# SR_Presentation_Version.net
KiCad netlist of a schematic drawn in EAGLE
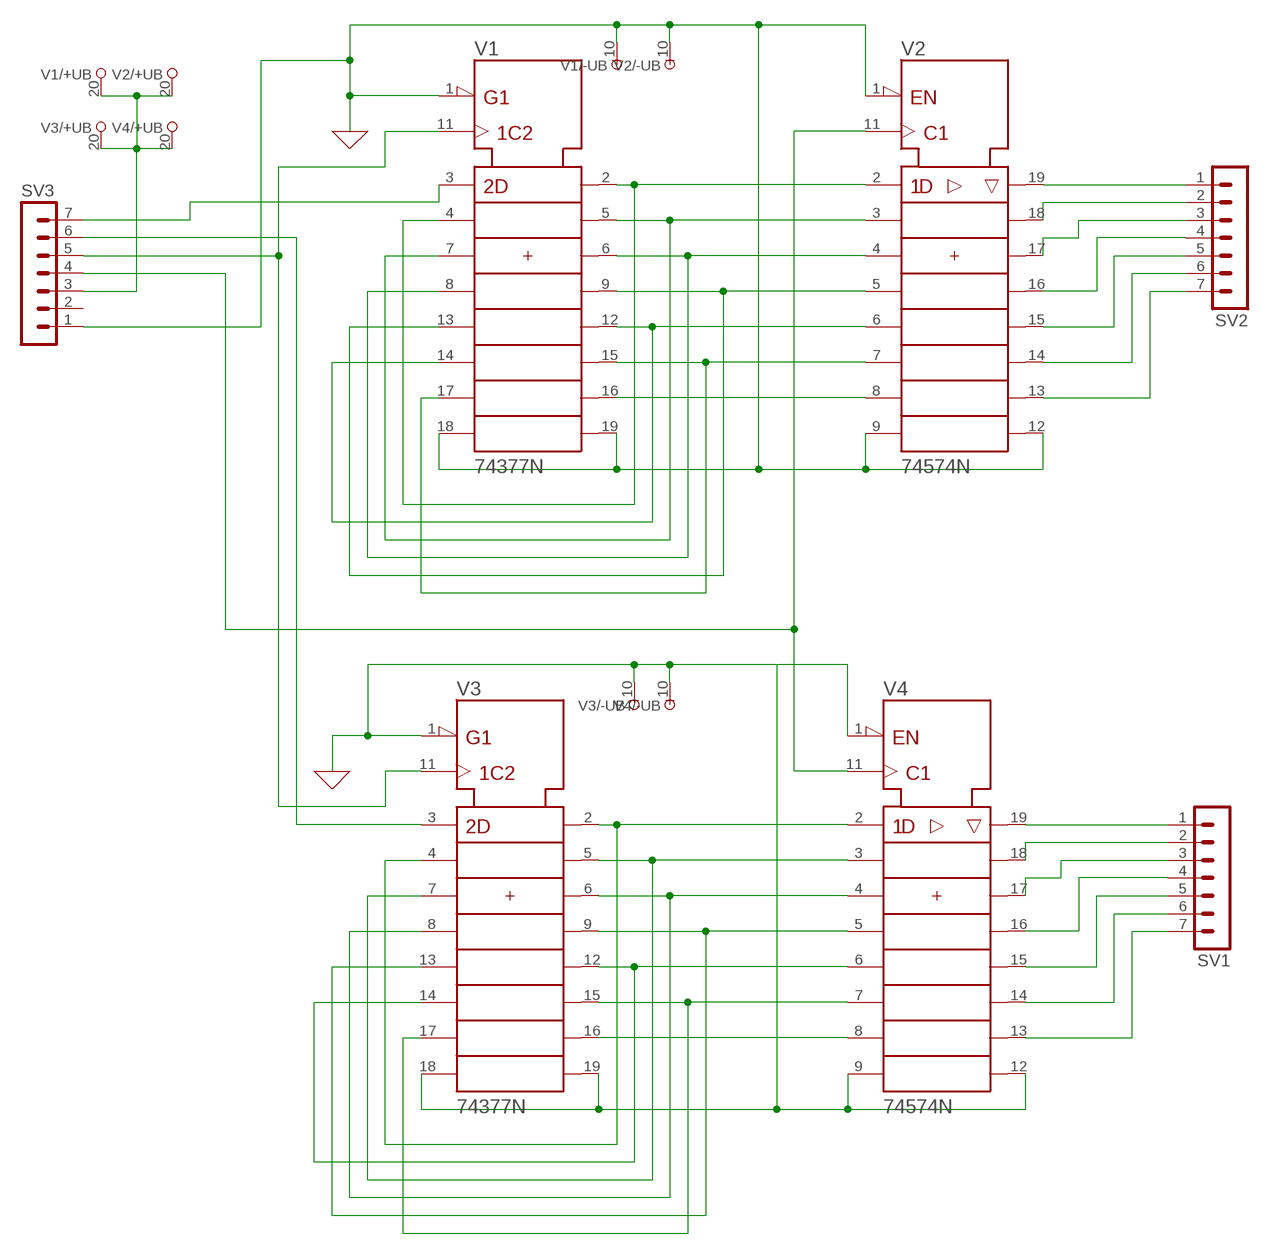
[diagram p0: schematic, sheet 1]

(export (version "E")
  (design (tool "Eeschema 10.0.6"))
  (components
    (comp (ref "SV1")
      (value "MA07-1")
      (footprint "eagle-import:MA07-1")
      (libsource (lib "eagle-import") (part "MA07-1"))
    )
    (comp (ref "SV2")
      (value "MA07-1")
      (footprint "eagle-import:MA07-1")
      (libsource (lib "eagle-import") (part "MA07-1"))
    )
    (comp (ref "SV3")
      (value "MA07-1")
      (footprint "eagle-import:MA07-1")
      (libsource (lib "eagle-import") (part "MA07-1"))
    )
    (comp (ref "V1")
      (value "74377N")
      (footprint "eagle-import:DIL20")
      (libsource (lib "eagle-import") (part "74377N"))
    )
    (comp (ref "V2")
      (value "74574N")
      (footprint "eagle-import:DIL20")
      (libsource (lib "eagle-import") (part "74574N"))
    )
    (comp (ref "V3")
      (value "74377N")
      (footprint "eagle-import:DIL20")
      (libsource (lib "eagle-import") (part "74377N"))
    )
    (comp (ref "V4")
      (value "74574N")
      (footprint "eagle-import:DIL20")
      (libsource (lib "eagle-import") (part "74574N"))
    )
  )
  (nets
    (net (code "1") (name "GND") (class "Default")
      (node (ref "SV3") (pin "1") (pinfunction "1_1") (pintype "passive"))
      (node (ref "V1") (pin "1") (pinfunction "~{G}_1") (pintype "input"))
      (node (ref "V1") (pin "10") (pinfunction "-UB_10") (pintype "power_in"))
      (node (ref "V1") (pin "18") (pinfunction "8D_18") (pintype "input"))
      (node (ref "V1") (pin "19") (pinfunction "8Q_19") (pintype "output"))
      (node (ref "V2") (pin "1") (pinfunction "~{OC}_1") (pintype "input"))
      (node (ref "V2") (pin "10") (pinfunction "-UB_10") (pintype "power_in"))
      (node (ref "V2") (pin "12") (pinfunction "8Q_12") (pintype "tri_state"))
      (node (ref "V2") (pin "9") (pinfunction "8D_9") (pintype "input"))
      (node (ref "V3") (pin "1") (pinfunction "~{G}_1") (pintype "input"))
      (node (ref "V3") (pin "10") (pinfunction "-UB_10") (pintype "power_in"))
      (node (ref "V3") (pin "18") (pinfunction "8D_18") (pintype "input"))
      (node (ref "V3") (pin "19") (pinfunction "8Q_19") (pintype "output"))
      (node (ref "V4") (pin "1") (pinfunction "~{OC}_1") (pintype "input"))
      (node (ref "V4") (pin "10") (pinfunction "-UB_10") (pintype "power_in"))
      (node (ref "V4") (pin "12") (pinfunction "8Q_12") (pintype "tri_state"))
      (node (ref "V4") (pin "9") (pinfunction "8D_9") (pintype "input"))
    )
    (net (code "2") (name "Net-(V1A-+UB)") (class "Default")
      (node (ref "SV3") (pin "3") (pinfunction "3_3") (pintype "passive"))
      (node (ref "V1") (pin "20") (pinfunction "+UB_20") (pintype "power_in"))
      (node (ref "V2") (pin "20") (pinfunction "+UB_20") (pintype "power_in"))
      (node (ref "V3") (pin "20") (pinfunction "+UB_20") (pintype "power_in"))
      (node (ref "V4") (pin "20") (pinfunction "+UB_20") (pintype "power_in"))
    )
    (net (code "3") (name "Net-(V1C-1D)") (class "Default")
      (node (ref "SV3") (pin "7") (pinfunction "7_7") (pintype "passive"))
      (node (ref "V1") (pin "3") (pinfunction "1D_3") (pintype "input"))
    )
    (net (code "4") (name "Net-(V1C-1Q)") (class "Default")
      (node (ref "V1") (pin "2") (pinfunction "1Q_2") (pintype "output"))
      (node (ref "V1") (pin "4") (pinfunction "2D_4") (pintype "input"))
      (node (ref "V2") (pin "2") (pinfunction "1D_2") (pintype "input"))
    )
    (net (code "5") (name "Net-(V1C-2Q)") (class "Default")
      (node (ref "V1") (pin "5") (pinfunction "2Q_5") (pintype "output"))
      (node (ref "V1") (pin "7") (pinfunction "3D_7") (pintype "input"))
      (node (ref "V2") (pin "3") (pinfunction "2D_3") (pintype "input"))
    )
    (net (code "6") (name "Net-(V1C-3Q)") (class "Default")
      (node (ref "V1") (pin "6") (pinfunction "3Q_6") (pintype "output"))
      (node (ref "V1") (pin "8") (pinfunction "4D_8") (pintype "input"))
      (node (ref "V2") (pin "4") (pinfunction "3D_4") (pintype "input"))
    )
    (net (code "7") (name "Net-(V1C-4Q)") (class "Default")
      (node (ref "V1") (pin "13") (pinfunction "5D_13") (pintype "input"))
      (node (ref "V1") (pin "9") (pinfunction "4Q_9") (pintype "output"))
      (node (ref "V2") (pin "5") (pinfunction "4D_5") (pintype "input"))
    )
    (net (code "8") (name "Net-(V1C-5Q)") (class "Default")
      (node (ref "V1") (pin "12") (pinfunction "5Q_12") (pintype "output"))
      (node (ref "V1") (pin "14") (pinfunction "6D_14") (pintype "input"))
      (node (ref "V2") (pin "6") (pinfunction "5D_6") (pintype "input"))
    )
    (net (code "9") (name "Net-(V1C-6Q)") (class "Default")
      (node (ref "V1") (pin "15") (pinfunction "6Q_15") (pintype "output"))
      (node (ref "V1") (pin "17") (pinfunction "7D_17") (pintype "input"))
      (node (ref "V2") (pin "7") (pinfunction "6D_7") (pintype "input"))
    )
    (net (code "10") (name "Net-(V1C-7Q)") (class "Default")
      (node (ref "V1") (pin "16") (pinfunction "7Q_16") (pintype "output"))
      (node (ref "V2") (pin "8") (pinfunction "7D_8") (pintype "input"))
    )
    (net (code "11") (name "Net-(V1C-CLK)") (class "Default")
      (node (ref "SV3") (pin "5") (pinfunction "5_5") (pintype "passive"))
      (node (ref "V1") (pin "11") (pinfunction "CLK_11") (pintype "input"))
      (node (ref "V3") (pin "11") (pinfunction "CLK_11") (pintype "input"))
    )
    (net (code "12") (name "Net-(V2C-1Q)") (class "Default")
      (node (ref "SV2") (pin "1") (pinfunction "1_1") (pintype "passive"))
      (node (ref "V2") (pin "19") (pinfunction "1Q_19") (pintype "tri_state"))
    )
    (net (code "13") (name "Net-(V2C-2Q)") (class "Default")
      (node (ref "SV2") (pin "2") (pinfunction "2_2") (pintype "passive"))
      (node (ref "V2") (pin "18") (pinfunction "2Q_18") (pintype "tri_state"))
    )
    (net (code "14") (name "Net-(V2C-3Q)") (class "Default")
      (node (ref "SV2") (pin "3") (pinfunction "3_3") (pintype "passive"))
      (node (ref "V2") (pin "17") (pinfunction "3Q_17") (pintype "tri_state"))
    )
    (net (code "15") (name "Net-(V2C-4Q)") (class "Default")
      (node (ref "SV2") (pin "4") (pinfunction "4_4") (pintype "passive"))
      (node (ref "V2") (pin "16") (pinfunction "4Q_16") (pintype "tri_state"))
    )
    (net (code "16") (name "Net-(V2C-5Q)") (class "Default")
      (node (ref "SV2") (pin "5") (pinfunction "5_5") (pintype "passive"))
      (node (ref "V2") (pin "15") (pinfunction "5Q_15") (pintype "tri_state"))
    )
    (net (code "17") (name "Net-(V2C-6Q)") (class "Default")
      (node (ref "SV2") (pin "6") (pinfunction "6_6") (pintype "passive"))
      (node (ref "V2") (pin "14") (pinfunction "6Q_14") (pintype "tri_state"))
    )
    (net (code "18") (name "Net-(V2C-7Q)") (class "Default")
      (node (ref "SV2") (pin "7") (pinfunction "7_7") (pintype "passive"))
      (node (ref "V2") (pin "13") (pinfunction "7Q_13") (pintype "tri_state"))
    )
    (net (code "19") (name "Net-(V2C-CLK)") (class "Default")
      (node (ref "SV3") (pin "4") (pinfunction "4_4") (pintype "passive"))
      (node (ref "V2") (pin "11") (pinfunction "CLK_11") (pintype "input"))
      (node (ref "V4") (pin "11") (pinfunction "CLK_11") (pintype "input"))
    )
    (net (code "20") (name "Net-(V3C-1D)") (class "Default")
      (node (ref "SV3") (pin "6") (pinfunction "6_6") (pintype "passive"))
      (node (ref "V3") (pin "3") (pinfunction "1D_3") (pintype "input"))
    )
    (net (code "21") (name "Net-(V3C-1Q)") (class "Default")
      (node (ref "V3") (pin "2") (pinfunction "1Q_2") (pintype "output"))
      (node (ref "V3") (pin "4") (pinfunction "2D_4") (pintype "input"))
      (node (ref "V4") (pin "2") (pinfunction "1D_2") (pintype "input"))
    )
    (net (code "22") (name "Net-(V3C-2Q)") (class "Default")
      (node (ref "V3") (pin "5") (pinfunction "2Q_5") (pintype "output"))
      (node (ref "V3") (pin "7") (pinfunction "3D_7") (pintype "input"))
      (node (ref "V4") (pin "3") (pinfunction "2D_3") (pintype "input"))
    )
    (net (code "23") (name "Net-(V3C-3Q)") (class "Default")
      (node (ref "V3") (pin "6") (pinfunction "3Q_6") (pintype "output"))
      (node (ref "V3") (pin "8") (pinfunction "4D_8") (pintype "input"))
      (node (ref "V4") (pin "4") (pinfunction "3D_4") (pintype "input"))
    )
    (net (code "24") (name "Net-(V3C-4Q)") (class "Default")
      (node (ref "V3") (pin "13") (pinfunction "5D_13") (pintype "input"))
      (node (ref "V3") (pin "9") (pinfunction "4Q_9") (pintype "output"))
      (node (ref "V4") (pin "5") (pinfunction "4D_5") (pintype "input"))
    )
    (net (code "25") (name "Net-(V3C-5Q)") (class "Default")
      (node (ref "V3") (pin "12") (pinfunction "5Q_12") (pintype "output"))
      (node (ref "V3") (pin "14") (pinfunction "6D_14") (pintype "input"))
      (node (ref "V4") (pin "6") (pinfunction "5D_6") (pintype "input"))
    )
    (net (code "26") (name "Net-(V3C-6Q)") (class "Default")
      (node (ref "V3") (pin "15") (pinfunction "6Q_15") (pintype "output"))
      (node (ref "V3") (pin "17") (pinfunction "7D_17") (pintype "input"))
      (node (ref "V4") (pin "7") (pinfunction "6D_7") (pintype "input"))
    )
    (net (code "27") (name "Net-(V3C-7Q)") (class "Default")
      (node (ref "V3") (pin "16") (pinfunction "7Q_16") (pintype "output"))
      (node (ref "V4") (pin "8") (pinfunction "7D_8") (pintype "input"))
    )
    (net (code "28") (name "Net-(V4C-1Q)") (class "Default")
      (node (ref "SV1") (pin "1") (pinfunction "1_1") (pintype "passive"))
      (node (ref "V4") (pin "19") (pinfunction "1Q_19") (pintype "tri_state"))
    )
    (net (code "29") (name "Net-(V4C-2Q)") (class "Default")
      (node (ref "SV1") (pin "2") (pinfunction "2_2") (pintype "passive"))
      (node (ref "V4") (pin "18") (pinfunction "2Q_18") (pintype "tri_state"))
    )
    (net (code "30") (name "Net-(V4C-3Q)") (class "Default")
      (node (ref "SV1") (pin "3") (pinfunction "3_3") (pintype "passive"))
      (node (ref "V4") (pin "17") (pinfunction "3Q_17") (pintype "tri_state"))
    )
    (net (code "31") (name "Net-(V4C-4Q)") (class "Default")
      (node (ref "SV1") (pin "4") (pinfunction "4_4") (pintype "passive"))
      (node (ref "V4") (pin "16") (pinfunction "4Q_16") (pintype "tri_state"))
    )
    (net (code "32") (name "Net-(V4C-5Q)") (class "Default")
      (node (ref "SV1") (pin "5") (pinfunction "5_5") (pintype "passive"))
      (node (ref "V4") (pin "15") (pinfunction "5Q_15") (pintype "tri_state"))
    )
    (net (code "33") (name "Net-(V4C-6Q)") (class "Default")
      (node (ref "SV1") (pin "6") (pinfunction "6_6") (pintype "passive"))
      (node (ref "V4") (pin "14") (pinfunction "6Q_14") (pintype "tri_state"))
    )
    (net (code "34") (name "Net-(V4C-7Q)") (class "Default")
      (node (ref "SV1") (pin "7") (pinfunction "7_7") (pintype "passive"))
      (node (ref "V4") (pin "13") (pinfunction "7Q_13") (pintype "tri_state"))
    )
    (net (code "35") (name "unconnected-(SV3-Pad2)") (class "Default")
      (node (ref "SV3") (pin "2") (pinfunction "2_2") (pintype "passive"))
    )
  )
)
